# coderbot_v5_0_rev_3.net
KiCad netlist of a schematic drawn in EAGLE
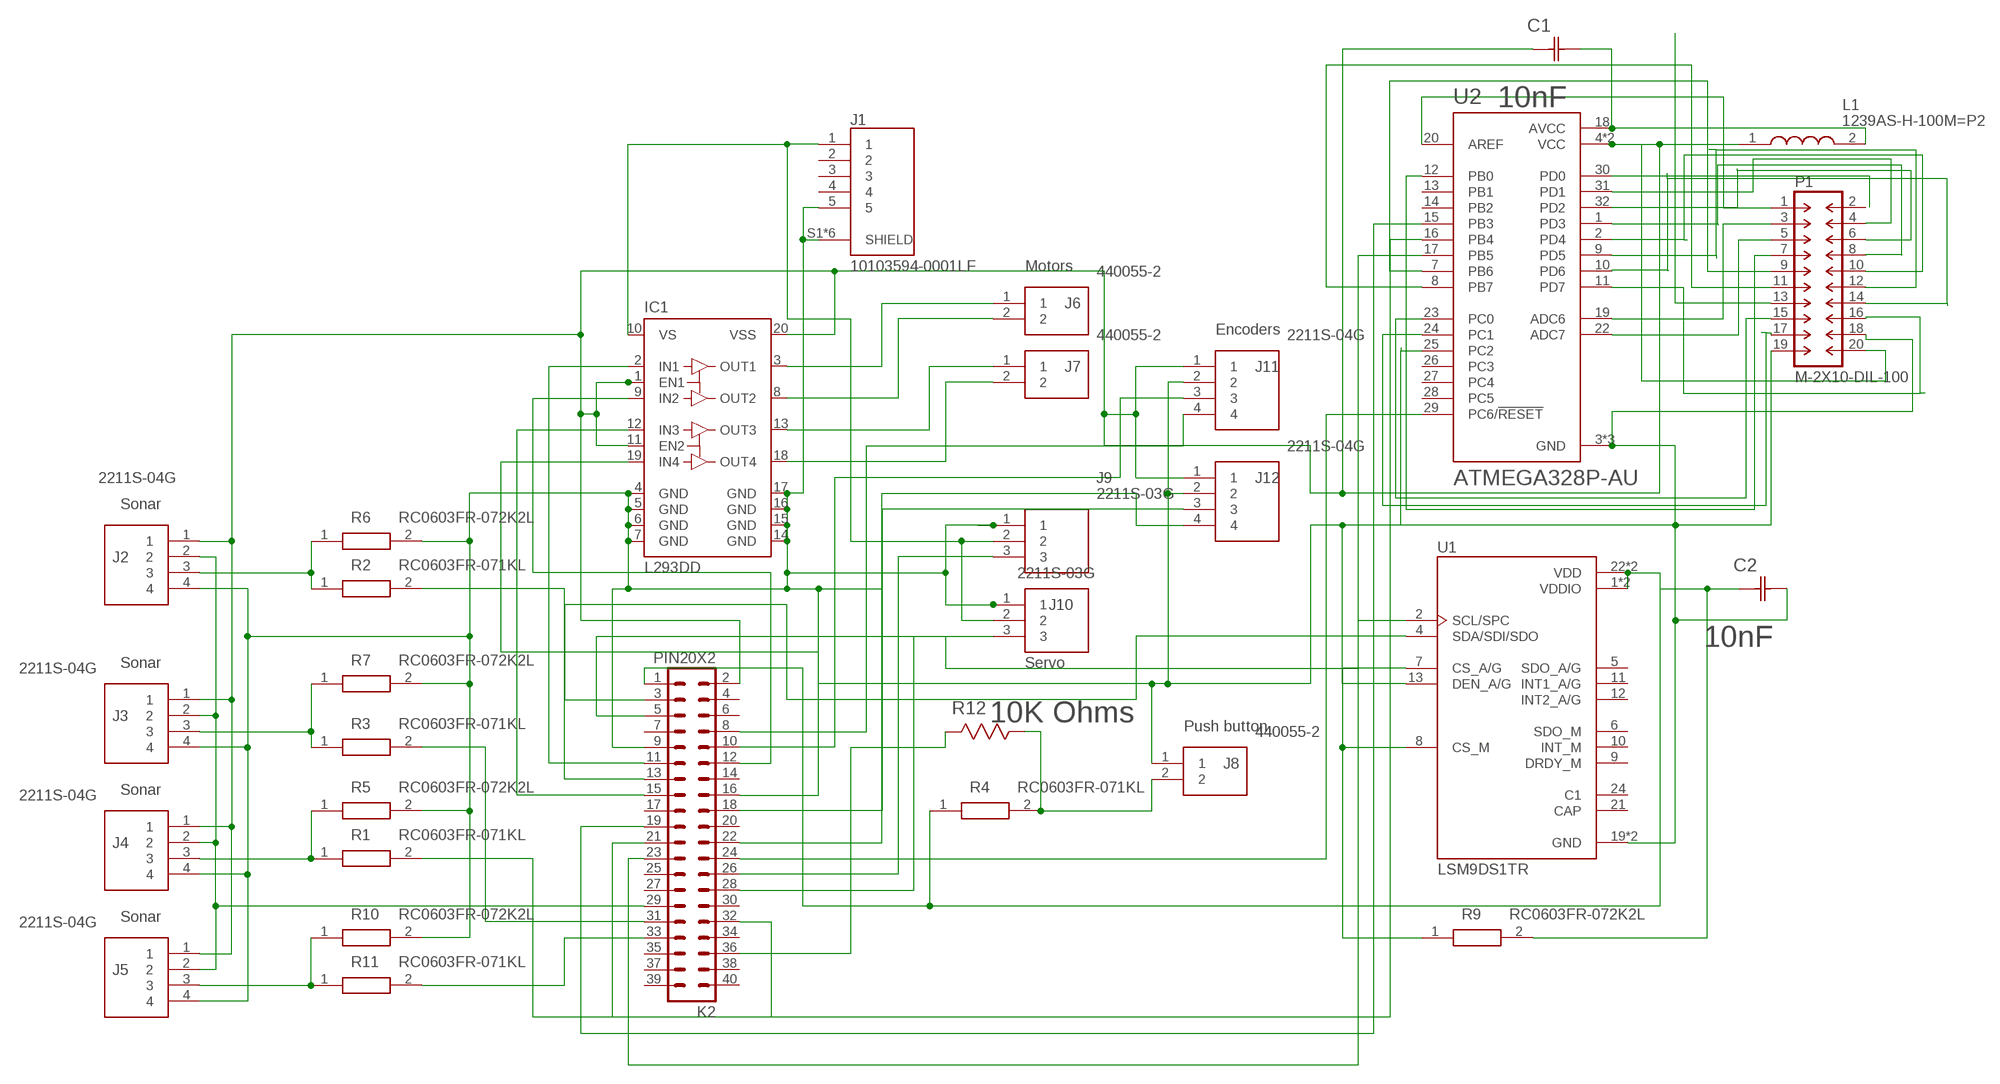
[diagram p0: schematic, sheet 1]

(export (version "E")
  (design (tool "Eeschema 10.0.6"))
  (components
    (comp (ref "C1")
      (value "10nF")
      (footprint "eagle-import:CAPC1005X55N")
      (fields (field (name "MPN") "CC0402KRX7R7BB103") (field (name "TOLERANCE") "±10%"))
      (libsource (lib "eagle-import") (part "CC0402KRX7R7BB103"))
    )
    (comp (ref "C2")
      (value "10nF")
      (footprint "eagle-import:CAPC1005X55N")
      (fields (field (name "MPN") "CC0402KRX7R7BB103") (field (name "TOLERANCE") "±10%"))
      (libsource (lib "eagle-import") (part "CC0402KRX7R7BB103"))
    )
    (comp (ref "IC1")
      (value "L293DD")
      (footprint "eagle-import:SO20")
      (libsource (lib "eagle-import") (part "L293DD"))
    )
    (comp (ref "J1")
      (value "10103594-0001LF")
      (footprint "eagle-import:FCI_10103594-0001LF")
      (fields (field (name "DIGI-KEY_PART_NUMBER") "609-4050-1-ND") (field (name "MF") "Amphenol ICC"))
      (libsource (lib "eagle-import") (part "10103594-0001LF"))
    )
    (comp (ref "J2")
      (value "2211S-04G")
      (footprint "eagle-import:HDRV4W90P0X254_1X4_1016X254X87")
      (libsource (lib "eagle-import") (part "2211S-04G"))
    )
    (comp (ref "J3")
      (value "2211S-04G")
      (footprint "eagle-import:HDRV4W90P0X254_1X4_1016X254X87")
      (libsource (lib "eagle-import") (part "2211S-04G"))
    )
    (comp (ref "J4")
      (value "2211S-04G")
      (footprint "eagle-import:HDRV4W90P0X254_1X4_1016X254X87")
      (libsource (lib "eagle-import") (part "2211S-04G"))
    )
    (comp (ref "J5")
      (value "2211S-04G")
      (footprint "eagle-import:HDRV4W90P0X254_1X4_1016X254X87")
      (libsource (lib "eagle-import") (part "2211S-04G"))
    )
    (comp (ref "J6")
      (value "440055-2")
      (footprint "eagle-import:SHDR2W70P0X200_1X2_600X770X525")
      (fields (field (name "MOUSER_PART_NUMBER") "571-440055-2"))
      (libsource (lib "eagle-import") (part "440055-2"))
    )
    (comp (ref "J7")
      (value "440055-2")
      (footprint "eagle-import:SHDR2W70P0X200_1X2_600X770X525")
      (fields (field (name "MOUSER_PART_NUMBER") "571-440055-2"))
      (libsource (lib "eagle-import") (part "440055-2"))
    )
    (comp (ref "J8")
      (value "440055-2")
      (footprint "eagle-import:SHDR2W70P0X200_1X2_600X770X525")
      (fields (field (name "MOUSER_PART_NUMBER") "571-440055-2"))
      (libsource (lib "eagle-import") (part "440055-2"))
    )
    (comp (ref "J9")
      (value "2211S-03G")
      (footprint "eagle-import:HDRV3W90P0X254_1X3_762X254X874")
      (libsource (lib "eagle-import") (part "2211S-03G"))
    )
    (comp (ref "J10")
      (value "2211S-03G")
      (footprint "eagle-import:HDRV3W90P0X254_1X3_762X254X874")
      (libsource (lib "eagle-import") (part "2211S-03G"))
    )
    (comp (ref "J11")
      (value "2211S-04G")
      (footprint "eagle-import:HDRV4W90P0X254_1X4_1016X254X87")
      (libsource (lib "eagle-import") (part "2211S-04G"))
    )
    (comp (ref "J12")
      (value "2211S-04G")
      (footprint "eagle-import:HDRV4W90P0X254_1X4_1016X254X87")
      (libsource (lib "eagle-import") (part "2211S-04G"))
    )
    (comp (ref "K2")
      (value "PIN20X2")
      (footprint "eagle-import:PIN_20X2")
      (libsource (lib "eagle-import") (part "PIN20X2"))
    )
    (comp (ref "L1")
      (value "1239AS-H-100M=P2")
      (footprint "eagle-import:INDC2520X120N")
      (fields
        (field (name "MOUSER_PART_NUMBER") "81-1239AS-H-100MP2")
        (field (name "RS_PART_NUMBER") "1453485")
      )
      (libsource (lib "eagle-import") (part "1239AS-H-100M=P2"))
    )
    (comp (ref "P1")
      (value "M-2X10-DIL-100")
      (footprint "eagle-import:DIL-100-2X10")
      (libsource (lib "eagle-import") (part "M-2X10-DIL-100"))
    )
    (comp (ref "R1")
      (value "RC0603FR-071KL")
      (footprint "eagle-import:RESC1608X55N")
      (fields
        (field (name "MOUSER_PART_NUMBER") "603-RC0603FR-071KL")
        (field (name "RS_PART_NUMBER") "5048928")
      )
      (libsource (lib "eagle-import") (part "RC0603FR-071KL"))
    )
    (comp (ref "R2")
      (value "RC0603FR-071KL")
      (footprint "eagle-import:RESC1608X55N")
      (fields
        (field (name "MOUSER_PART_NUMBER") "603-RC0603FR-071KL")
        (field (name "RS_PART_NUMBER") "5048928")
      )
      (libsource (lib "eagle-import") (part "RC0603FR-071KL"))
    )
    (comp (ref "R3")
      (value "RC0603FR-071KL")
      (footprint "eagle-import:RESC1608X55N")
      (fields
        (field (name "MOUSER_PART_NUMBER") "603-RC0603FR-071KL")
        (field (name "RS_PART_NUMBER") "5048928")
      )
      (libsource (lib "eagle-import") (part "RC0603FR-071KL"))
    )
    (comp (ref "R4")
      (value "RC0603FR-071KL")
      (footprint "eagle-import:RESC1608X55N")
      (fields
        (field (name "MOUSER_PART_NUMBER") "603-RC0603FR-071KL")
        (field (name "RS_PART_NUMBER") "5048928")
      )
      (libsource (lib "eagle-import") (part "RC0603FR-071KL"))
    )
    (comp (ref "R5")
      (value "RC0603FR-072K2L")
      (footprint "eagle-import:RESC1608X55N")
      (fields
        (field (name "MOUSER_PART_NUMBER") "603-RC0603FR-072K2L")
        (field (name "RS_PART_NUMBER") "5050319")
      )
      (libsource (lib "eagle-import") (part "RC0603FR-072K2L"))
    )
    (comp (ref "R6")
      (value "RC0603FR-072K2L")
      (footprint "eagle-import:RESC1608X55N")
      (fields
        (field (name "MOUSER_PART_NUMBER") "603-RC0603FR-072K2L")
        (field (name "RS_PART_NUMBER") "5050319")
      )
      (libsource (lib "eagle-import") (part "RC0603FR-072K2L"))
    )
    (comp (ref "R7")
      (value "RC0603FR-072K2L")
      (footprint "eagle-import:RESC1608X55N")
      (fields
        (field (name "MOUSER_PART_NUMBER") "603-RC0603FR-072K2L")
        (field (name "RS_PART_NUMBER") "5050319")
      )
      (libsource (lib "eagle-import") (part "RC0603FR-072K2L"))
    )
    (comp (ref "R9")
      (value "RC0603FR-072K2L")
      (footprint "eagle-import:RESC1608X55N")
      (fields
        (field (name "MOUSER_PART_NUMBER") "603-RC0603FR-072K2L")
        (field (name "RS_PART_NUMBER") "5050319")
      )
      (libsource (lib "eagle-import") (part "RC0603FR-072K2L"))
    )
    (comp (ref "R10")
      (value "RC0603FR-072K2L")
      (footprint "eagle-import:RESC1608X55N")
      (fields
        (field (name "MOUSER_PART_NUMBER") "603-RC0603FR-072K2L")
        (field (name "RS_PART_NUMBER") "5050319")
      )
      (libsource (lib "eagle-import") (part "RC0603FR-072K2L"))
    )
    (comp (ref "R11")
      (value "RC0603FR-071KL")
      (footprint "eagle-import:RESC1608X55N")
      (fields
        (field (name "MOUSER_PART_NUMBER") "603-RC0603FR-071KL")
        (field (name "RS_PART_NUMBER") "5048928")
      )
      (libsource (lib "eagle-import") (part "RC0603FR-071KL"))
    )
    (comp (ref "R12")
      (value "10K Ohms")
      (footprint "eagle-import:RESC1608X60N")
      (fields (field (name "MPN") "RC0603FR-0710KL") (field (name "TOLERANCE") "±1%"))
      (libsource (lib "eagle-import") (part "RC0603FR-0710KL"))
    )
    (comp (ref "U1")
      (value "LSM9DS1TR")
      (footprint "eagle-import:PQFN43P300X350X102-24N")
      (fields (field (name "MF") "STMicroelectronics"))
      (libsource (lib "eagle-import") (part "LSM9DS1TR"))
    )
    (comp (ref "U2")
      (value "ATMEGA328P-AU")
      (footprint "eagle-import:QFP80P900X900X120-32N")
      (fields (field (name "MF") "Microchip"))
      (libsource (lib "eagle-import") (part "ATMEGA328P-AU"))
    )
  )
  (nets
    (net (code "1") (name "Net-(C1-C1)") (class "Default")
      (node (ref "C1") (pin "1") (pinfunction "C1_1") (pintype "passive"))
      (node (ref "IC1") (pin "1") (pinfunction "EN1_1") (pintype "input"))
      (node (ref "IC1") (pin "11") (pinfunction "EN2_11") (pintype "input"))
      (node (ref "IC1") (pin "20") (pinfunction "VSS_20") (pintype "power_in"))
      (node (ref "J11") (pin "1") (pinfunction "1_1") (pintype "bidirectional"))
      (node (ref "J12") (pin "1") (pinfunction "1_1") (pintype "bidirectional"))
      (node (ref "J2") (pin "1") (pinfunction "1_1") (pintype "bidirectional"))
      (node (ref "J3") (pin "1") (pinfunction "1_1") (pintype "bidirectional"))
      (node (ref "J4") (pin "1") (pinfunction "1_1") (pintype "bidirectional"))
      (node (ref "J5") (pin "1") (pinfunction "1_1") (pintype "bidirectional"))
      (node (ref "K2") (pin "2") (pinfunction "2_2") (pintype "passive"))
      (node (ref "L1") (pin "1") (pinfunction "1_1") (pintype "bidirectional"))
      (node (ref "P1") (pin "20") (pinfunction "20_20") (pintype "passive"))
      (node (ref "U2") (pin "4") (pinfunction "VCC_4") (pintype "power_in"))
      (node (ref "U2") (pin "6") (pinfunction "VCC_6") (pintype "power_in"))
    )
    (net (code "2") (name "Net-(C1-C2)") (class "Default")
      (node (ref "C1") (pin "2") (pinfunction "C2_2") (pintype "passive"))
      (node (ref "L1") (pin "2") (pinfunction "2_2") (pintype "bidirectional"))
      (node (ref "U2") (pin "18") (pinfunction "AVCC_18") (pintype "power_in"))
    )
    (net (code "3") (name "Net-(C2-C1)") (class "Default")
      (node (ref "C2") (pin "1") (pinfunction "C1_1") (pintype "passive"))
      (node (ref "K2") (pin "1") (pinfunction "1_1") (pintype "passive"))
      (node (ref "R4") (pin "1") (pinfunction "1_1") (pintype "bidirectional"))
      (node (ref "R9") (pin "2") (pinfunction "2_2") (pintype "bidirectional"))
      (node (ref "U1") (pin "1") (pinfunction "VDDIO_1") (pintype "power_in"))
      (node (ref "U1") (pin "22") (pinfunction "VDD_22") (pintype "power_in"))
      (node (ref "U1") (pin "23") (pinfunction "VDD_23") (pintype "power_in"))
      (node (ref "U1") (pin "3") (pinfunction "VDDIO_3") (pintype "power_in"))
    )
    (net (code "4") (name "Net-(C2-C2)") (class "Default")
      (node (ref "C2") (pin "2") (pinfunction "C2_2") (pintype "passive"))
      (node (ref "IC1") (pin "14") (pinfunction "GND_14") (pintype "power_in"))
      (node (ref "IC1") (pin "15") (pinfunction "GND_15") (pintype "power_in"))
      (node (ref "IC1") (pin "16") (pinfunction "GND_16") (pintype "power_in"))
      (node (ref "IC1") (pin "17") (pinfunction "GND_17") (pintype "power_in"))
      (node (ref "IC1") (pin "4") (pinfunction "GND_4") (pintype "power_in"))
      (node (ref "IC1") (pin "5") (pinfunction "GND_5") (pintype "power_in"))
      (node (ref "IC1") (pin "6") (pinfunction "GND_6") (pintype "power_in"))
      (node (ref "IC1") (pin "7") (pinfunction "GND_7") (pintype "power_in"))
      (node (ref "J1") (pin "5") (pinfunction "5_5") (pintype "passive"))
      (node (ref "J1") (pin "S1") (pinfunction "SHIELD_S1") (pintype "passive"))
      (node (ref "J1") (pin "S2") (pinfunction "SHIELD_S2") (pintype "passive"))
      (node (ref "J1") (pin "S3") (pinfunction "SHIELD_S3") (pintype "passive"))
      (node (ref "J1") (pin "S4") (pinfunction "SHIELD_S4") (pintype "passive"))
      (node (ref "J1") (pin "S5") (pinfunction "SHIELD_S5") (pintype "passive"))
      (node (ref "J1") (pin "S6") (pinfunction "SHIELD_S6") (pintype "passive"))
      (node (ref "J10") (pin "1") (pinfunction "1_1") (pintype "bidirectional"))
      (node (ref "J11") (pin "2") (pinfunction "2_2") (pintype "bidirectional"))
      (node (ref "J12") (pin "2") (pinfunction "2_2") (pintype "bidirectional"))
      (node (ref "J2") (pin "4") (pinfunction "4_4") (pintype "bidirectional"))
      (node (ref "J3") (pin "4") (pinfunction "4_4") (pintype "bidirectional"))
      (node (ref "J4") (pin "4") (pinfunction "4_4") (pintype "bidirectional"))
      (node (ref "J5") (pin "4") (pinfunction "4_4") (pintype "bidirectional"))
      (node (ref "J8") (pin "1") (pinfunction "1_1") (pintype "bidirectional"))
      (node (ref "J9") (pin "1") (pinfunction "1_1") (pintype "bidirectional"))
      (node (ref "K2") (pin "9") (pinfunction "9_9") (pintype "passive"))
      (node (ref "P1") (pin "18") (pinfunction "18_18") (pintype "passive"))
      (node (ref "R10") (pin "2") (pinfunction "2_2") (pintype "bidirectional"))
      (node (ref "R5") (pin "2") (pinfunction "2_2") (pintype "bidirectional"))
      (node (ref "R6") (pin "2") (pinfunction "2_2") (pintype "bidirectional"))
      (node (ref "R7") (pin "2") (pinfunction "2_2") (pintype "bidirectional"))
      (node (ref "U1") (pin "13") (pinfunction "DEN_A/G_13") (pintype "input"))
      (node (ref "U1") (pin "19") (pinfunction "GND_19") (pintype "power_in"))
      (node (ref "U1") (pin "20") (pinfunction "GND_20") (pintype "power_in"))
      (node (ref "U2") (pin "21") (pinfunction "GND_21") (pintype "power_in"))
      (node (ref "U2") (pin "3") (pinfunction "GND_3") (pintype "power_in"))
      (node (ref "U2") (pin "5") (pinfunction "GND_5") (pintype "power_in"))
    )
    (net (code "5") (name "Net-(IC1-IN1)") (class "Default")
      (node (ref "IC1") (pin "2") (pinfunction "IN1_2") (pintype "input"))
      (node (ref "K2") (pin "11") (pinfunction "11_11") (pintype "passive"))
    )
    (net (code "6") (name "Net-(IC1-IN2)") (class "Default")
      (node (ref "IC1") (pin "9") (pinfunction "IN2_9") (pintype "input"))
      (node (ref "K2") (pin "12") (pinfunction "12_12") (pintype "passive"))
    )
    (net (code "7") (name "Net-(IC1-IN3)") (class "Default")
      (node (ref "IC1") (pin "12") (pinfunction "IN3_12") (pintype "input"))
      (node (ref "K2") (pin "15") (pinfunction "15_15") (pintype "passive"))
    )
    (net (code "8") (name "Net-(IC1-IN4)") (class "Default")
      (node (ref "IC1") (pin "19") (pinfunction "IN4_19") (pintype "input"))
      (node (ref "K2") (pin "16") (pinfunction "16_16") (pintype "passive"))
    )
    (net (code "9") (name "Net-(IC1-OUT1)") (class "Default")
      (node (ref "IC1") (pin "3") (pinfunction "OUT1_3") (pintype "output"))
      (node (ref "J6") (pin "1") (pinfunction "1_1") (pintype "bidirectional"))
    )
    (net (code "10") (name "Net-(IC1-OUT2)") (class "Default")
      (node (ref "IC1") (pin "8") (pinfunction "OUT2_8") (pintype "output"))
      (node (ref "J6") (pin "2") (pinfunction "2_2") (pintype "bidirectional"))
    )
    (net (code "11") (name "Net-(IC1-OUT3)") (class "Default")
      (node (ref "IC1") (pin "13") (pinfunction "OUT3_13") (pintype "output"))
      (node (ref "J7") (pin "1") (pinfunction "1_1") (pintype "bidirectional"))
    )
    (net (code "12") (name "Net-(IC1-OUT4)") (class "Default")
      (node (ref "IC1") (pin "18") (pinfunction "OUT4_18") (pintype "output"))
      (node (ref "J7") (pin "2") (pinfunction "2_2") (pintype "bidirectional"))
    )
    (net (code "13") (name "Net-(IC1-VS)") (class "Default")
      (node (ref "IC1") (pin "10") (pinfunction "VS_10") (pintype "power_in"))
      (node (ref "J1") (pin "1") (pinfunction "1_1") (pintype "passive"))
      (node (ref "J10") (pin "2") (pinfunction "2_2") (pintype "bidirectional"))
      (node (ref "J9") (pin "2") (pinfunction "2_2") (pintype "bidirectional"))
    )
    (net (code "14") (name "Net-(J2-Pad2)") (class "Default")
      (node (ref "J2") (pin "2") (pinfunction "2_2") (pintype "bidirectional"))
      (node (ref "J3") (pin "2") (pinfunction "2_2") (pintype "bidirectional"))
      (node (ref "J4") (pin "2") (pinfunction "2_2") (pintype "bidirectional"))
      (node (ref "J5") (pin "2") (pinfunction "2_2") (pintype "bidirectional"))
      (node (ref "K2") (pin "29") (pinfunction "29_29") (pintype "passive"))
    )
    (net (code "15") (name "Net-(J2-Pad3)") (class "Default")
      (node (ref "J2") (pin "3") (pinfunction "3_3") (pintype "bidirectional"))
      (node (ref "R2") (pin "1") (pinfunction "1_1") (pintype "bidirectional"))
      (node (ref "R6") (pin "1") (pinfunction "1_1") (pintype "bidirectional"))
    )
    (net (code "16") (name "Net-(J3-Pad3)") (class "Default")
      (node (ref "J3") (pin "3") (pinfunction "3_3") (pintype "bidirectional"))
      (node (ref "R3") (pin "1") (pinfunction "1_1") (pintype "bidirectional"))
      (node (ref "R7") (pin "1") (pinfunction "1_1") (pintype "bidirectional"))
    )
    (net (code "17") (name "Net-(J4-Pad3)") (class "Default")
      (node (ref "J4") (pin "3") (pinfunction "3_3") (pintype "bidirectional"))
      (node (ref "R1") (pin "1") (pinfunction "1_1") (pintype "bidirectional"))
      (node (ref "R5") (pin "1") (pinfunction "1_1") (pintype "bidirectional"))
    )
    (net (code "18") (name "Net-(J5-Pad3)") (class "Default")
      (node (ref "J5") (pin "3") (pinfunction "3_3") (pintype "bidirectional"))
      (node (ref "R10") (pin "1") (pinfunction "1_1") (pintype "bidirectional"))
      (node (ref "R11") (pin "1") (pinfunction "1_1") (pintype "bidirectional"))
    )
    (net (code "19") (name "Net-(J9-Pad3)") (class "Default")
      (node (ref "J9") (pin "3") (pinfunction "3_3") (pintype "bidirectional"))
      (node (ref "K2") (pin "26") (pinfunction "26_26") (pintype "passive"))
    )
    (net (code "20") (name "Net-(J10-Pad3)") (class "Default")
      (node (ref "J10") (pin "3") (pinfunction "3_3") (pintype "bidirectional"))
      (node (ref "K2") (pin "28") (pinfunction "28_28") (pintype "passive"))
    )
    (net (code "21") (name "Net-(J11-Pad3)") (class "Default")
      (node (ref "J11") (pin "3") (pinfunction "3_3") (pintype "bidirectional"))
      (node (ref "K2") (pin "10") (pinfunction "10_10") (pintype "passive"))
    )
    (net (code "22") (name "Net-(J11-Pad4)") (class "Default")
      (node (ref "J11") (pin "4") (pinfunction "4_4") (pintype "bidirectional"))
      (node (ref "K2") (pin "8") (pinfunction "8_8") (pintype "passive"))
    )
    (net (code "23") (name "Net-(J12-Pad3)") (class "Default")
      (node (ref "J12") (pin "3") (pinfunction "3_3") (pintype "bidirectional"))
      (node (ref "K2") (pin "18") (pinfunction "18_18") (pintype "passive"))
    )
    (net (code "24") (name "Net-(J12-Pad4)") (class "Default")
      (node (ref "J12") (pin "4") (pinfunction "4_4") (pintype "bidirectional"))
      (node (ref "K2") (pin "22") (pinfunction "22_22") (pintype "passive"))
    )
    (net (code "25") (name "Net-(K2-Pad13)") (class "Default")
      (node (ref "K2") (pin "13") (pinfunction "13_13") (pintype "passive"))
      (node (ref "R2") (pin "2") (pinfunction "2_2") (pintype "bidirectional"))
    )
    (net (code "26") (name "Net-(K2-Pad31)") (class "Default")
      (node (ref "K2") (pin "31") (pinfunction "31_31") (pintype "passive"))
      (node (ref "R3") (pin "2") (pinfunction "2_2") (pintype "bidirectional"))
    )
    (net (code "27") (name "Net-(K2-Pad32)") (class "Default")
      (node (ref "K2") (pin "32") (pinfunction "32_32") (pintype "passive"))
      (node (ref "R1") (pin "2") (pinfunction "2_2") (pintype "bidirectional"))
    )
    (net (code "28") (name "Net-(K2-Pad33)") (class "Default")
      (node (ref "K2") (pin "33") (pinfunction "33_33") (pintype "passive"))
      (node (ref "R11") (pin "2") (pinfunction "2_2") (pintype "bidirectional"))
    )
    (net (code "29") (name "Net-(R12-R1)") (class "Default")
      (node (ref "J8") (pin "2") (pinfunction "2_2") (pintype "bidirectional"))
      (node (ref "R12") (pin "1") (pinfunction "R1_1") (pintype "passive"))
      (node (ref "R4") (pin "2") (pinfunction "2_2") (pintype "bidirectional"))
    )
    (net (code "30") (name "Net-(R12-R2)") (class "Default")
      (node (ref "K2") (pin "36") (pinfunction "36_36") (pintype "passive"))
      (node (ref "R12") (pin "2") (pinfunction "R2_2") (pintype "passive"))
    )
    (net (code "31") (name "Net-(U1-CS_A{slash}G)") (class "Default")
      (node (ref "R9") (pin "1") (pinfunction "1_1") (pintype "bidirectional"))
      (node (ref "U1") (pin "7") (pinfunction "CS_A/G_7") (pintype "input"))
      (node (ref "U1") (pin "8") (pinfunction "CS_M_8") (pintype "input"))
    )
    (net (code "32") (name "Net-(U1-SCL{slash}SPC)") (class "Default")
      (node (ref "K2") (pin "5") (pinfunction "5_5") (pintype "passive"))
      (node (ref "U1") (pin "2") (pinfunction "SCL/SPC_2") (pintype "input"))
    )
    (net (code "33") (name "Net-(U1-SDA{slash}SDI{slash}SDO)") (class "Default")
      (node (ref "K2") (pin "3") (pinfunction "3_3") (pintype "passive"))
      (node (ref "U1") (pin "4") (pinfunction "SDA/SDI/SDO_4") (pintype "bidirectional"))
    )
    (net (code "34") (name "Net-(U2-ADC6)") (class "Default")
      (node (ref "P1") (pin "3") (pinfunction "3_3") (pintype "passive"))
      (node (ref "U2") (pin "19") (pinfunction "ADC6_19") (pintype "bidirectional"))
    )
    (net (code "35") (name "Net-(U2-ADC7)") (class "Default")
      (node (ref "P1") (pin "5") (pinfunction "5_5") (pintype "passive"))
      (node (ref "U2") (pin "22") (pinfunction "ADC7_22") (pintype "bidirectional"))
    )
    (net (code "36") (name "Net-(U2-AREF)") (class "Default")
      (node (ref "P1") (pin "1") (pinfunction "1_1") (pintype "passive"))
      (node (ref "U2") (pin "20") (pinfunction "AREF_20") (pintype "input"))
    )
    (net (code "37") (name "Net-(U2-PB0)") (class "Default")
      (node (ref "P1") (pin "7") (pinfunction "7_7") (pintype "passive"))
      (node (ref "U2") (pin "12") (pinfunction "PB0_12") (pintype "bidirectional"))
    )
    (net (code "38") (name "Net-(U2-PB3)") (class "Default")
      (node (ref "K2") (pin "19") (pinfunction "19_19") (pintype "passive"))
      (node (ref "U2") (pin "15") (pinfunction "PB3_15") (pintype "bidirectional"))
    )
    (net (code "39") (name "Net-(U2-PB4)") (class "Default")
      (node (ref "K2") (pin "21") (pinfunction "21_21") (pintype "passive"))
      (node (ref "U2") (pin "16") (pinfunction "PB4_16") (pintype "bidirectional"))
    )
    (net (code "40") (name "Net-(U2-PB5)") (class "Default")
      (node (ref "K2") (pin "23") (pinfunction "23_23") (pintype "passive"))
      (node (ref "U2") (pin "17") (pinfunction "PB5_17") (pintype "bidirectional"))
    )
    (net (code "41") (name "Net-(U2-PB6)") (class "Default")
      (node (ref "P1") (pin "9") (pinfunction "9_9") (pintype "passive"))
      (node (ref "U2") (pin "7") (pinfunction "PB6_7") (pintype "bidirectional"))
    )
    (net (code "42") (name "Net-(U2-PB7)") (class "Default")
      (node (ref "P1") (pin "11") (pinfunction "11_11") (pintype "passive"))
      (node (ref "U2") (pin "8") (pinfunction "PB7_8") (pintype "bidirectional"))
    )
    (net (code "43") (name "Net-(U2-PC0)") (class "Default")
      (node (ref "P1") (pin "15") (pinfunction "15_15") (pintype "passive"))
      (node (ref "U2") (pin "23") (pinfunction "PC0_23") (pintype "bidirectional"))
    )
    (net (code "44") (name "Net-(U2-PC1)") (class "Default")
      (node (ref "P1") (pin "17") (pinfunction "17_17") (pintype "passive"))
      (node (ref "U2") (pin "24") (pinfunction "PC1_24") (pintype "bidirectional"))
    )
    (net (code "45") (name "Net-(U2-PC2)") (class "Default")
      (node (ref "P1") (pin "19") (pinfunction "19_19") (pintype "passive"))
      (node (ref "U2") (pin "25") (pinfunction "PC2_25") (pintype "bidirectional"))
    )
    (net (code "46") (name "Net-(U2-PC6{slash}~{RESET})") (class "Default")
      (node (ref "K2") (pin "24") (pinfunction "24_24") (pintype "passive"))
      (node (ref "U2") (pin "29") (pinfunction "PC6/~{RESET}_29") (pintype "bidirectional"))
    )
    (net (code "47") (name "Net-(U2-PD1)") (class "Default")
      (node (ref "P1") (pin "4") (pinfunction "4_4") (pintype "passive"))
      (node (ref "U2") (pin "31") (pinfunction "PD1_31") (pintype "bidirectional"))
    )
    (net (code "48") (name "Net-(U2-PD2)") (class "Default")
      (node (ref "P1") (pin "6") (pinfunction "6_6") (pintype "passive"))
      (node (ref "U2") (pin "32") (pinfunction "PD2_32") (pintype "bidirectional"))
    )
    (net (code "49") (name "Net-(U2-PD3)") (class "Default")
      (node (ref "P1") (pin "8") (pinfunction "8_8") (pintype "passive"))
      (node (ref "U2") (pin "1") (pinfunction "PD3_1") (pintype "bidirectional"))
    )
    (net (code "50") (name "Net-(U2-PD4)") (class "Default")
      (node (ref "P1") (pin "10") (pinfunction "10_10") (pintype "passive"))
      (node (ref "U2") (pin "2") (pinfunction "PD4_2") (pintype "bidirectional"))
    )
    (net (code "51") (name "Net-(U2-PD5)") (class "Default")
      (node (ref "P1") (pin "12") (pinfunction "12_12") (pintype "passive"))
      (node (ref "U2") (pin "9") (pinfunction "PD5_9") (pintype "bidirectional"))
    )
    (net (code "52") (name "Net-(U2-PD6)") (class "Default")
      (node (ref "P1") (pin "14") (pinfunction "14_14") (pintype "passive"))
      (node (ref "U2") (pin "10") (pinfunction "PD6_10") (pintype "bidirectional"))
    )
    (net (code "53") (name "Net-(U2-PD7)") (class "Default")
      (node (ref "P1") (pin "16") (pinfunction "16_16") (pintype "passive"))
      (node (ref "U2") (pin "11") (pinfunction "PD7_11") (pintype "bidirectional"))
    )
    (net (code "54") (name "unconnected-(J1-Pad2)") (class "Default")
      (node (ref "J1") (pin "2") (pinfunction "2_2") (pintype "passive"))
    )
    (net (code "55") (name "unconnected-(J1-Pad3)") (class "Default")
      (node (ref "J1") (pin "3") (pinfunction "3_3") (pintype "passive"))
    )
    (net (code "56") (name "unconnected-(J1-Pad4)") (class "Default")
      (node (ref "J1") (pin "4") (pinfunction "4_4") (pintype "passive"))
    )
    (net (code "57") (name "unconnected-(K2-Pad4)") (class "Default")
      (node (ref "K2") (pin "4") (pinfunction "4_4") (pintype "passive"))
    )
    (net (code "58") (name "unconnected-(K2-Pad6)") (class "Default")
      (node (ref "K2") (pin "6") (pinfunction "6_6") (pintype "passive"))
    )
    (net (code "59") (name "unconnected-(K2-Pad7)") (class "Default")
      (node (ref "K2") (pin "7") (pinfunction "7_7") (pintype "passive"))
    )
    (net (code "60") (name "unconnected-(K2-Pad14)") (class "Default")
      (node (ref "K2") (pin "14") (pinfunction "14_14") (pintype "passive"))
    )
    (net (code "61") (name "unconnected-(K2-Pad17)") (class "Default")
      (node (ref "K2") (pin "17") (pinfunction "17_17") (pintype "passive"))
    )
    (net (code "62") (name "unconnected-(K2-Pad20)") (class "Default")
      (node (ref "K2") (pin "20") (pinfunction "20_20") (pintype "passive"))
    )
    (net (code "63") (name "unconnected-(K2-Pad25)") (class "Default")
      (node (ref "K2") (pin "25") (pinfunction "25_25") (pintype "passive"))
    )
    (net (code "64") (name "unconnected-(K2-Pad27)") (class "Default")
      (node (ref "K2") (pin "27") (pinfunction "27_27") (pintype "passive"))
    )
    (net (code "65") (name "unconnected-(K2-Pad30)") (class "Default")
      (node (ref "K2") (pin "30") (pinfunction "30_30") (pintype "passive"))
    )
    (net (code "66") (name "unconnected-(K2-Pad34)") (class "Default")
      (node (ref "K2") (pin "34") (pinfunction "34_34") (pintype "passive"))
    )
    (net (code "67") (name "unconnected-(K2-Pad35)") (class "Default")
      (node (ref "K2") (pin "35") (pinfunction "35_35") (pintype "passive"))
    )
    (net (code "68") (name "unconnected-(K2-Pad37)") (class "Default")
      (node (ref "K2") (pin "37") (pinfunction "37_37") (pintype "passive"))
    )
    (net (code "69") (name "unconnected-(K2-Pad38)") (class "Default")
      (node (ref "K2") (pin "38") (pinfunction "38_38") (pintype "passive"))
    )
    (net (code "70") (name "unconnected-(K2-Pad39)") (class "Default")
      (node (ref "K2") (pin "39") (pinfunction "39_39") (pintype "passive"))
    )
    (net (code "71") (name "unconnected-(K2-Pad40)") (class "Default")
      (node (ref "K2") (pin "40") (pinfunction "40_40") (pintype "passive"))
    )
    (net (code "72") (name "unconnected-(P1-Pad2)") (class "Default")
      (node (ref "P1") (pin "2") (pinfunction "2_2") (pintype "passive"))
    )
    (net (code "73") (name "unconnected-(P1-Pad13)") (class "Default")
      (node (ref "P1") (pin "13") (pinfunction "13_13") (pintype "passive"))
    )
    (net (code "74") (name "unconnected-(U1-C1-Pad24)") (class "Default")
      (node (ref "U1") (pin "24") (pinfunction "C1_24") (pintype "passive"))
    )
    (net (code "75") (name "unconnected-(U1-CAP-Pad21)") (class "Default")
      (node (ref "U1") (pin "21") (pinfunction "CAP_21") (pintype "passive"))
    )
    (net (code "76") (name "unconnected-(U1-DRDY_M-Pad9)") (class "Default")
      (node (ref "U1") (pin "9") (pinfunction "DRDY_M_9") (pintype "output"))
    )
    (net (code "77") (name "unconnected-(U1-INT1_A{slash}G-Pad11)") (class "Default")
      (node (ref "U1") (pin "11") (pinfunction "INT1_A/G_11") (pintype "output"))
    )
    (net (code "78") (name "unconnected-(U1-INT2_A{slash}G-Pad12)") (class "Default")
      (node (ref "U1") (pin "12") (pinfunction "INT2_A/G_12") (pintype "output"))
    )
    (net (code "79") (name "unconnected-(U1-INT_M-Pad10)") (class "Default")
      (node (ref "U1") (pin "10") (pinfunction "INT_M_10") (pintype "output"))
    )
    (net (code "80") (name "unconnected-(U1-SDO_A{slash}G-Pad5)") (class "Default")
      (node (ref "U1") (pin "5") (pinfunction "SDO_A/G_5") (pintype "output"))
    )
    (net (code "81") (name "unconnected-(U1-SDO_M-Pad6)") (class "Default")
      (node (ref "U1") (pin "6") (pinfunction "SDO_M_6") (pintype "output"))
    )
    (net (code "82") (name "unconnected-(U2-PB1-Pad13)") (class "Default")
      (node (ref "U2") (pin "13") (pinfunction "PB1_13") (pintype "bidirectional"))
    )
    (net (code "83") (name "unconnected-(U2-PB2-Pad14)") (class "Default")
      (node (ref "U2") (pin "14") (pinfunction "PB2_14") (pintype "bidirectional"))
    )
    (net (code "84") (name "unconnected-(U2-PC3-Pad26)") (class "Default")
      (node (ref "U2") (pin "26") (pinfunction "PC3_26") (pintype "bidirectional"))
    )
    (net (code "85") (name "unconnected-(U2-PC4-Pad27)") (class "Default")
      (node (ref "U2") (pin "27") (pinfunction "PC4_27") (pintype "bidirectional"))
    )
    (net (code "86") (name "unconnected-(U2-PC5-Pad28)") (class "Default")
      (node (ref "U2") (pin "28") (pinfunction "PC5_28") (pintype "bidirectional"))
    )
    (net (code "87") (name "unconnected-(U2-PD0-Pad30)") (class "Default")
      (node (ref "U2") (pin "30") (pinfunction "PD0_30") (pintype "bidirectional"))
    )
  )
)
